# MB_TOP.net
KiCad netlist of a schematic drawn in Altium Designer
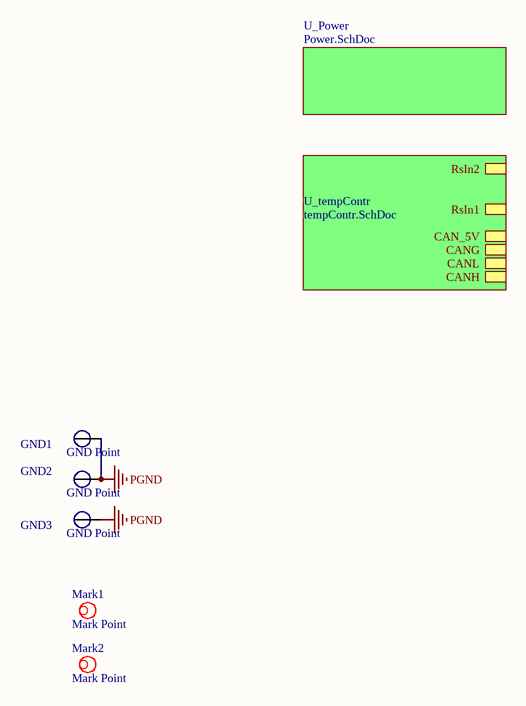
[diagram p0: MB_TOP.SchDoc]

(export (version "E")
  (design (tool "Eeschema 10.0.6"))
  (components
    (comp (ref "GND1")
      (value "GND Point")
      (footprint "Gnd_Point")
      (libsource (lib "CON1") (part "GND_Point"))
    )
    (comp (ref "GND2")
      (value "GND Point")
      (footprint "Gnd_Point")
      (libsource (lib "CON1") (part "GND_Point"))
    )
    (comp (ref "GND3")
      (value "GND Point")
      (footprint "Gnd_Point")
      (libsource (lib "CON1") (part "GND_Point"))
    )
    (comp (ref "Mark1") (value "Mark Point") (footprint "MARK 3mm") (libsource (lib "CON1") (part "MARK")))
    (comp (ref "Mark2") (value "Mark Point") (footprint "MARK 3mm") (libsource (lib "CON1") (part "MARK")))
  )
  (nets
    (net (code "7") (name "PGND") (class "Default")
      (node (ref "GND1") (pin "1") (pinfunction "GND_1") (pintype "passive"))
      (node (ref "GND2") (pin "1") (pinfunction "GND_1") (pintype "passive"))
      (node (ref "GND3") (pin "1") (pinfunction "GND_1") (pintype "passive"))
    )
  )
)
